# LogicCircuits_main.net
KiCad netlist of a schematic drawn in Altium Designer
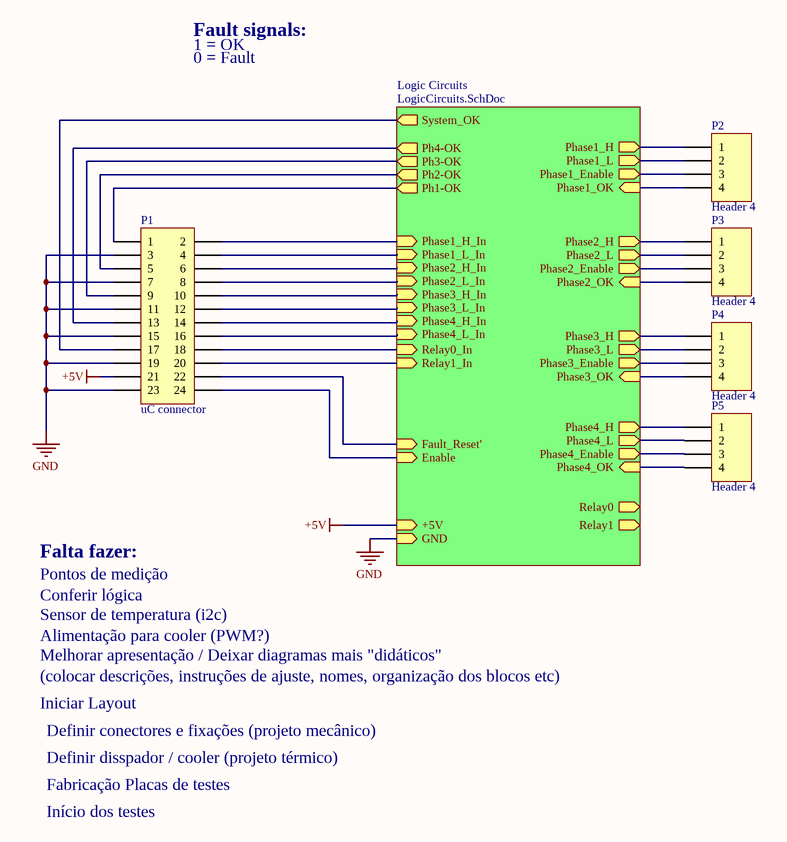
[diagram p0: LogicCircuits_main.SchDoc]

(export (version "E")
  (design (tool "Eeschema 10.0.6"))
  (components
    (comp (ref "P1")
      (value "uC connector")
      (footprint "HDR2X12")
      (description "Header, 12-Pin, Dual row")
      (fields (field (name "PUBLISHER") "Altium Limited"))
      (libsource (lib "Miscellaneous Connectors") (part "Header 12X2"))
    )
    (comp (ref "P2")
      (value "Header 4")
      (footprint "HDR1X4")
      (description "Header, 4-Pin")
      (fields (field (name "PUBLISHER") "Altium Limited"))
      (libsource (lib "Miscellaneous Connectors") (part "Header 4"))
    )
    (comp (ref "P3")
      (value "Header 4")
      (footprint "HDR1X4")
      (description "Header, 4-Pin")
      (fields (field (name "PUBLISHER") "Altium Limited"))
      (libsource (lib "Miscellaneous Connectors") (part "Header 4"))
    )
    (comp (ref "P4")
      (value "Header 4")
      (footprint "HDR1X4")
      (description "Header, 4-Pin")
      (fields (field (name "PUBLISHER") "Altium Limited"))
      (libsource (lib "Miscellaneous Connectors") (part "Header 4"))
    )
    (comp (ref "P5")
      (value "Header 4")
      (footprint "HDR1X4")
      (description "Header, 4-Pin")
      (fields (field (name "PUBLISHER") "Altium Limited"))
      (libsource (lib "Miscellaneous Connectors") (part "Header 4"))
    )
  )
  (nets
    (net (code "1") (name "+5V") (class "Default")
      (node (ref "P1") (pin "21") (pinfunction "21_21") (pintype "passive"))
    )
    (net (code "2") (name "/Enable") (class "Default")
      (node (ref "P1") (pin "24") (pinfunction "24_24") (pintype "passive"))
    )
    (net (code "3") (name "/Fault_Reset'") (class "Default")
      (node (ref "P1") (pin "22") (pinfunction "22_22") (pintype "passive"))
    )
    (net (code "4") (name "/Ph1-OK") (class "Default")
      (node (ref "P1") (pin "1") (pinfunction "1_1") (pintype "passive"))
    )
    (net (code "5") (name "/Ph2-OK") (class "Default")
      (node (ref "P1") (pin "5") (pinfunction "5_5") (pintype "passive"))
    )
    (net (code "6") (name "/Ph3-OK") (class "Default")
      (node (ref "P1") (pin "9") (pinfunction "9_9") (pintype "passive"))
    )
    (net (code "7") (name "/Ph4-OK") (class "Default")
      (node (ref "P1") (pin "13") (pinfunction "13_13") (pintype "passive"))
    )
    (net (code "8") (name "/Phase1_Enable") (class "Default")
      (node (ref "P2") (pin "3") (pinfunction "3_3") (pintype "passive"))
    )
    (net (code "9") (name "/Phase1_H") (class "Default")
      (node (ref "P2") (pin "1") (pinfunction "1_1") (pintype "passive"))
    )
    (net (code "10") (name "/Phase1_H_In") (class "Default")
      (node (ref "P1") (pin "2") (pinfunction "2_2") (pintype "passive"))
    )
    (net (code "11") (name "/Phase1_L") (class "Default")
      (node (ref "P2") (pin "2") (pinfunction "2_2") (pintype "passive"))
    )
    (net (code "12") (name "/Phase1_L_In") (class "Default")
      (node (ref "P1") (pin "4") (pinfunction "4_4") (pintype "passive"))
    )
    (net (code "13") (name "/Phase1_OK") (class "Default")
      (node (ref "P2") (pin "4") (pinfunction "4_4") (pintype "passive"))
    )
    (net (code "14") (name "/Phase2_Enable") (class "Default")
      (node (ref "P3") (pin "3") (pinfunction "3_3") (pintype "passive"))
    )
    (net (code "15") (name "/Phase2_H") (class "Default")
      (node (ref "P3") (pin "1") (pinfunction "1_1") (pintype "passive"))
    )
    (net (code "16") (name "/Phase2_H_In") (class "Default")
      (node (ref "P1") (pin "6") (pinfunction "6_6") (pintype "passive"))
    )
    (net (code "17") (name "/Phase2_L") (class "Default")
      (node (ref "P3") (pin "2") (pinfunction "2_2") (pintype "passive"))
    )
    (net (code "18") (name "/Phase2_L_In") (class "Default")
      (node (ref "P1") (pin "8") (pinfunction "8_8") (pintype "passive"))
    )
    (net (code "19") (name "/Phase2_OK") (class "Default")
      (node (ref "P3") (pin "4") (pinfunction "4_4") (pintype "passive"))
    )
    (net (code "20") (name "/Phase3_Enable") (class "Default")
      (node (ref "P4") (pin "3") (pinfunction "3_3") (pintype "passive"))
    )
    (net (code "21") (name "/Phase3_H") (class "Default")
      (node (ref "P4") (pin "1") (pinfunction "1_1") (pintype "passive"))
    )
    (net (code "22") (name "/Phase3_H_In") (class "Default")
      (node (ref "P1") (pin "10") (pinfunction "10_10") (pintype "passive"))
    )
    (net (code "23") (name "/Phase3_L") (class "Default")
      (node (ref "P4") (pin "2") (pinfunction "2_2") (pintype "passive"))
    )
    (net (code "24") (name "/Phase3_L_In") (class "Default")
      (node (ref "P1") (pin "12") (pinfunction "12_12") (pintype "passive"))
    )
    (net (code "25") (name "/Phase3_OK") (class "Default")
      (node (ref "P4") (pin "4") (pinfunction "4_4") (pintype "passive"))
    )
    (net (code "26") (name "/Phase4_Enable") (class "Default")
      (node (ref "P5") (pin "3") (pinfunction "3_3") (pintype "passive"))
    )
    (net (code "27") (name "/Phase4_H") (class "Default")
      (node (ref "P5") (pin "1") (pinfunction "1_1") (pintype "passive"))
    )
    (net (code "28") (name "/Phase4_H_In") (class "Default")
      (node (ref "P1") (pin "14") (pinfunction "14_14") (pintype "passive"))
    )
    (net (code "29") (name "/Phase4_L") (class "Default")
      (node (ref "P5") (pin "2") (pinfunction "2_2") (pintype "passive"))
    )
    (net (code "30") (name "/Phase4_L_In") (class "Default")
      (node (ref "P1") (pin "16") (pinfunction "16_16") (pintype "passive"))
    )
    (net (code "31") (name "/Phase4_OK") (class "Default")
      (node (ref "P5") (pin "4") (pinfunction "4_4") (pintype "passive"))
    )
    (net (code "33") (name "/Relay0_In") (class "Default")
      (node (ref "P1") (pin "18") (pinfunction "18_18") (pintype "passive"))
    )
    (net (code "35") (name "/Relay1_In") (class "Default")
      (node (ref "P1") (pin "20") (pinfunction "20_20") (pintype "passive"))
    )
    (net (code "36") (name "/System_OK") (class "Default")
      (node (ref "P1") (pin "17") (pinfunction "17_17") (pintype "passive"))
    )
    (net (code "37") (name "GND") (class "Default")
      (node (ref "P1") (pin "11") (pinfunction "11_11") (pintype "passive"))
      (node (ref "P1") (pin "15") (pinfunction "15_15") (pintype "passive"))
      (node (ref "P1") (pin "19") (pinfunction "19_19") (pintype "passive"))
      (node (ref "P1") (pin "23") (pinfunction "23_23") (pintype "passive"))
      (node (ref "P1") (pin "3") (pinfunction "3_3") (pintype "passive"))
      (node (ref "P1") (pin "7") (pinfunction "7_7") (pintype "passive"))
    )
  )
)
